# A300_Backplane.net
KiCad netlist of a schematic drawn in Altium Designer
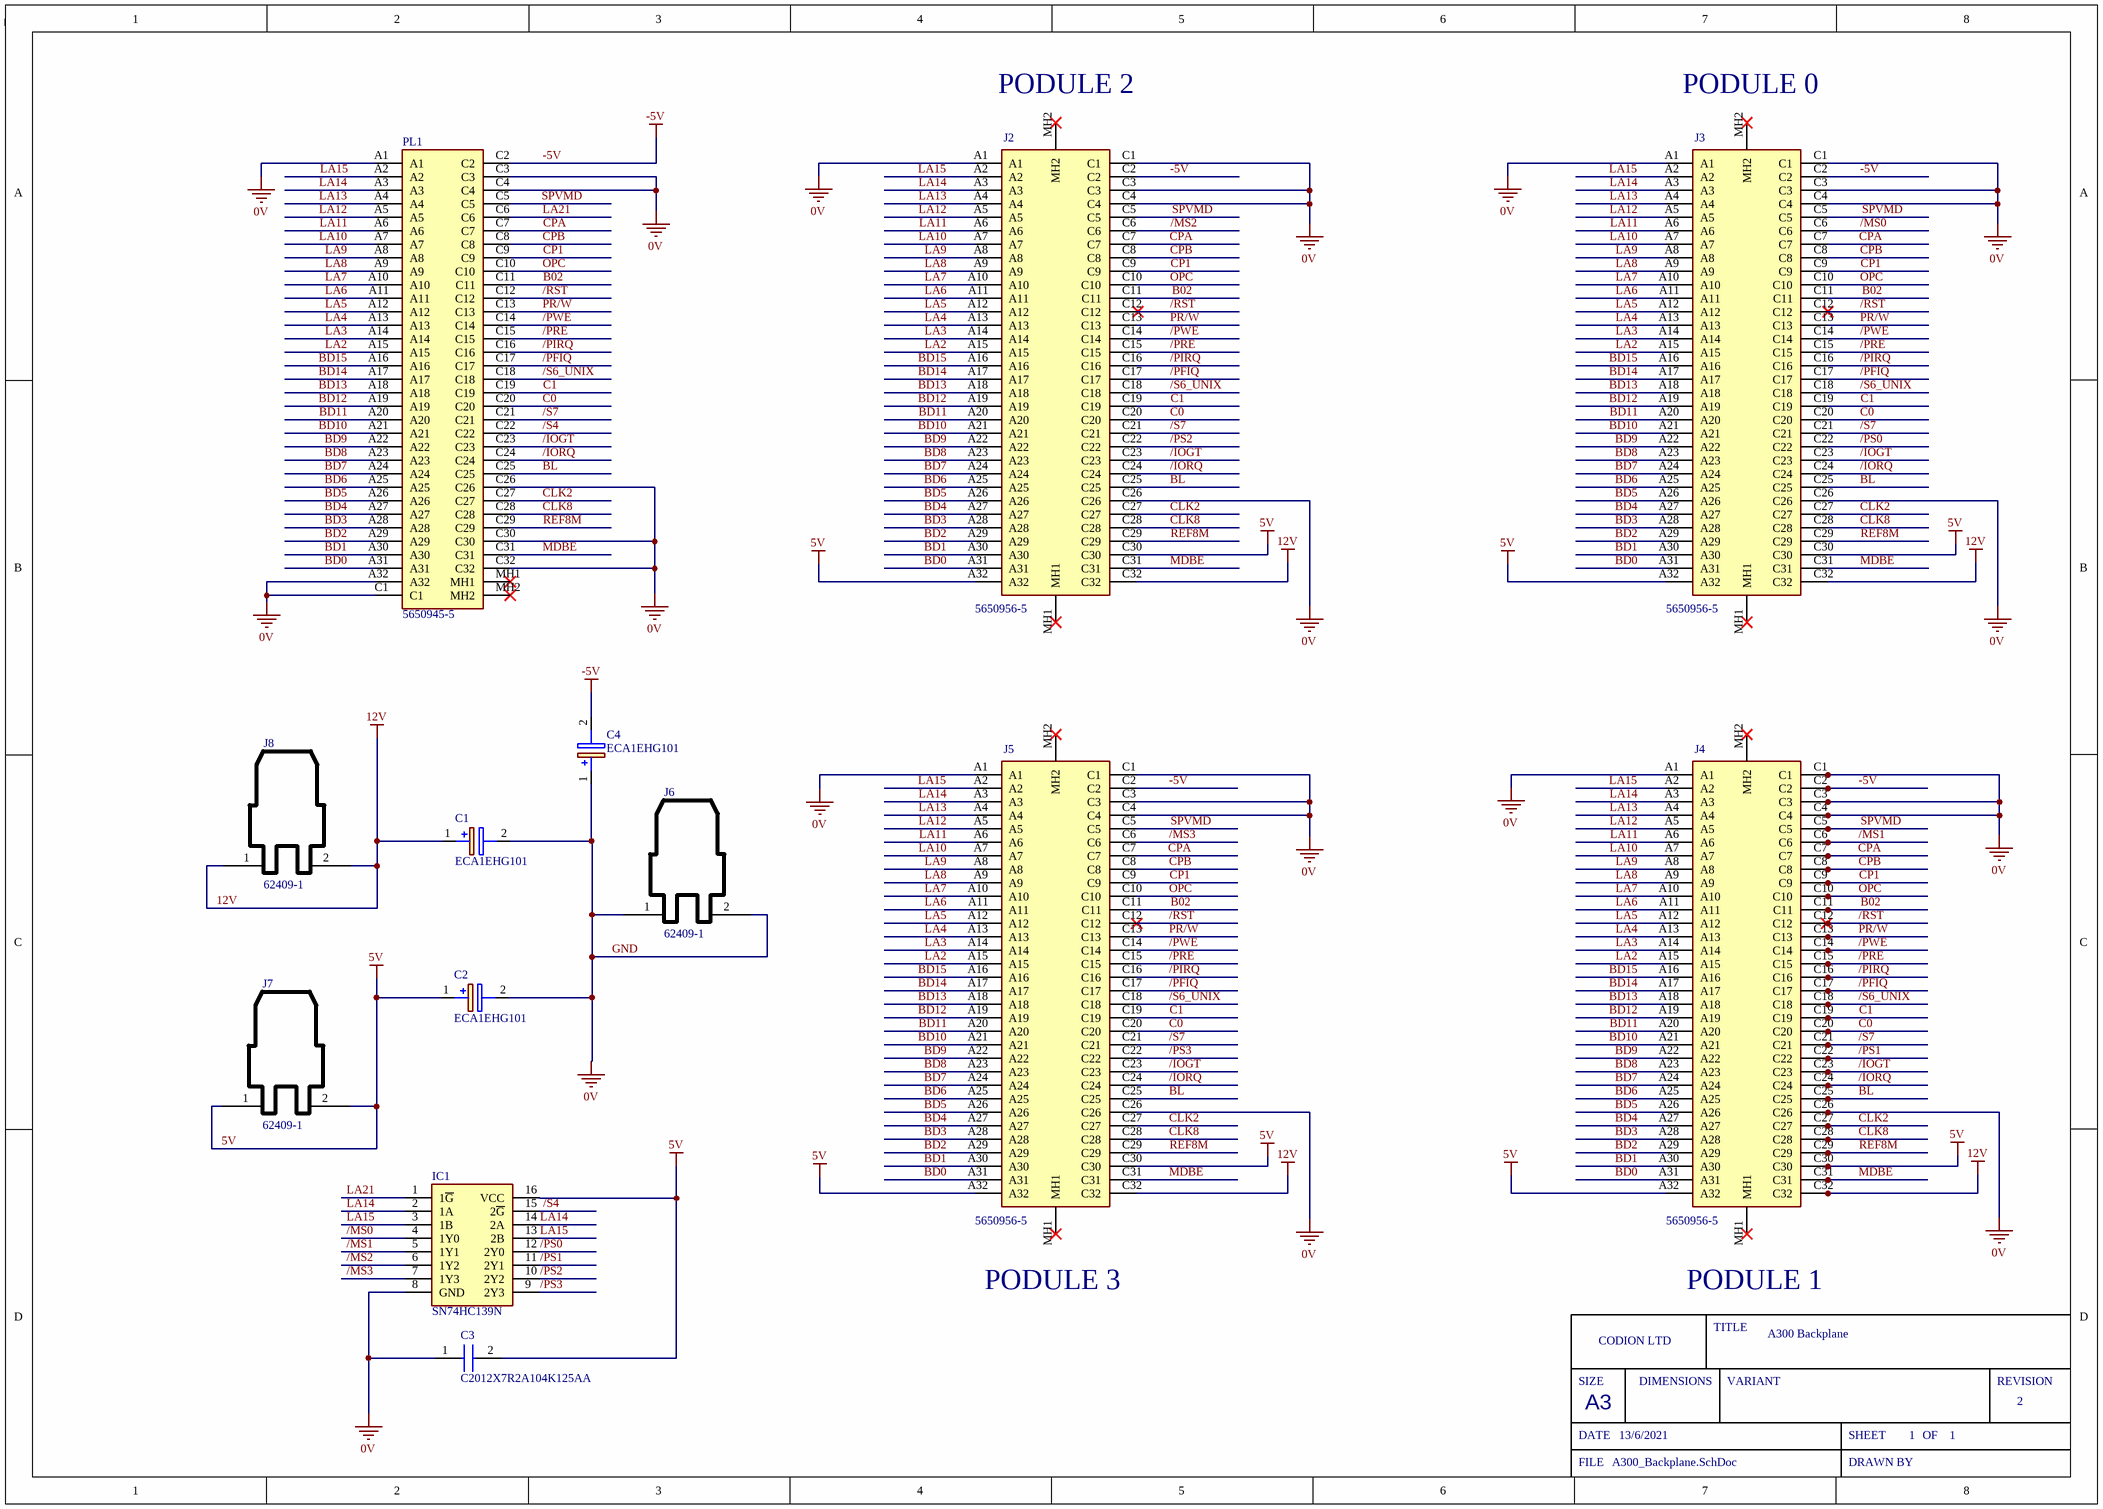
[diagram p0: A300_Backplane.SchDoc]

(export (version "E")
  (design (tool "Eeschema 10.0.6"))
  (components
    (comp (ref "C1")
      (value "ECA1EHG101")
      (footprint "SamacSys:CAPPRD250W55D630H1220")
      (description "Capacitor Polarised")
      (libsource (lib "*") (part "ECA1EHG101"))
    )
    (comp (ref "C2")
      (value "ECA1EHG101")
      (footprint "SamacSys:CAPPRD250W55D630H1220")
      (description "Capacitor Polarised")
      (libsource (lib "*") (part "ECA1EHG101"))
    )
    (comp (ref "C3")
      (value "C2012X7R2A104K125AA")
      (footprint "SamacSys:CAPC2012X145N")
      (description "Capacitor")
      (fields (field (name "MOUSER PART NUMBER") "810-C2012X7R2A104K"))
      (libsource (lib "*") (part "C2012X7R2A104K125AA"))
    )
    (comp (ref "C4")
      (value "ECA1EHG101")
      (footprint "SamacSys:CAPPRD250W55D630H1220")
      (description "Capacitor Polarised")
      (libsource (lib "") (part "ECA1EHG101_1"))
    )
    (comp (ref "IC1")
      (value "SN74HC139N")
      (footprint "SamacSys:DIP794W53P254L1930H508Q16N")
      (description "Integrated Circuit")
      (fields (field (name "MOUSER PART NUMBER") "595-SN74HC139N"))
      (libsource (lib "*") (part "SN74HC139N"))
    )
    (comp (ref "J2")
      (value "5650956-5")
      (footprint "SamacSys:56509565")
      (description "Connector")
      (fields (field (name "MOUSER PART NUMBER") "571-5650956-5"))
      (libsource (lib "*") (part "5650956-5"))
    )
    (comp (ref "J3")
      (value "5650956-5")
      (footprint "SamacSys:56509565")
      (description "Connector")
      (fields (field (name "MOUSER PART NUMBER") "571-5650956-5"))
      (libsource (lib "*") (part "5650956-5"))
    )
    (comp (ref "J4")
      (value "5650956-5")
      (footprint "SamacSys:56509565")
      (description "Connector")
      (fields (field (name "MOUSER PART NUMBER") "571-5650956-5"))
      (libsource (lib "*") (part "5650956-5"))
    )
    (comp (ref "J5")
      (value "5650956-5")
      (footprint "SamacSys:56509565")
      (description "Connector")
      (fields (field (name "MOUSER PART NUMBER") "571-5650956-5"))
      (libsource (lib "*") (part "5650956-5"))
    )
    (comp (ref "J6")
      (value "62409-1")
      (footprint "62409-1")
      (description "PCB Terminal, 6.35mm x 0.81mm, 0.25\" x 0.032\", Brass, 1.4 mm, Tin")
      (fields (field (name "PART NUMBER") "982-0022") (field (name "MANUFACTURER") "TE Coonectivity"))
      (libsource (lib "Local_Altium_Lib") (part "62409-1"))
    )
    (comp (ref "J7")
      (value "62409-1")
      (footprint "62409-1")
      (description "PCB Terminal, 6.35mm x 0.81mm, 0.25\" x 0.032\", Brass, 1.4 mm, Tin")
      (fields (field (name "PART NUMBER") "982-0022") (field (name "MANUFACTURER") "TE Coonectivity"))
      (libsource (lib "Local_Altium_Lib") (part "62409-1"))
    )
    (comp (ref "J8")
      (value "62409-1")
      (footprint "62409-1")
      (description "PCB Terminal, 6.35mm x 0.81mm, 0.25\" x 0.032\", Brass, 1.4 mm, Tin")
      (fields (field (name "PART NUMBER") "982-0022") (field (name "MANUFACTURER") "TE Coonectivity"))
      (libsource (lib "Local_Altium_Lib") (part "62409-1"))
    )
    (comp (ref "PL1")
      (value "5650945-5")
      (footprint "SamacSys:56509455")
      (description "Connector")
      (fields (field (name "MOUSER PART NUMBER") "571-5650945-5"))
      (libsource (lib "*") (part "5650945-5"))
    )
  )
  (nets
    (net (code "1") (name "-5V") (class "Default")
      (node (ref "C4") (pin "2") (pinfunction "-_2") (pintype "passive"))
      (node (ref "J2") (pin "C2") (pinfunction "C2_C2") (pintype "passive"))
      (node (ref "J3") (pin "C2") (pinfunction "C2_C2") (pintype "passive"))
      (node (ref "J4") (pin "C2") (pinfunction "C2_C2") (pintype "passive"))
      (node (ref "J5") (pin "C2") (pinfunction "C2_C2") (pintype "passive"))
      (node (ref "PL1") (pin "C2") (pinfunction "C2_C2") (pintype "passive"))
    )
    (net (code "2") (name "/B02") (class "Default")
      (node (ref "J2") (pin "C11") (pinfunction "C11_C11") (pintype "passive"))
      (node (ref "J3") (pin "C11") (pinfunction "C11_C11") (pintype "passive"))
      (node (ref "J4") (pin "C11") (pinfunction "C11_C11") (pintype "passive"))
      (node (ref "J5") (pin "C11") (pinfunction "C11_C11") (pintype "passive"))
      (node (ref "PL1") (pin "C11") (pinfunction "C11_C11") (pintype "passive"))
    )
    (net (code "3") (name "/BD0") (class "Default")
      (node (ref "J2") (pin "A31") (pinfunction "A31_A31") (pintype "passive"))
      (node (ref "J3") (pin "A31") (pinfunction "A31_A31") (pintype "passive"))
      (node (ref "J4") (pin "A31") (pinfunction "A31_A31") (pintype "passive"))
      (node (ref "J5") (pin "A31") (pinfunction "A31_A31") (pintype "passive"))
      (node (ref "PL1") (pin "A31") (pinfunction "A31_A31") (pintype "passive"))
    )
    (net (code "4") (name "/BD1") (class "Default")
      (node (ref "J2") (pin "A30") (pinfunction "A30_A30") (pintype "passive"))
      (node (ref "J3") (pin "A30") (pinfunction "A30_A30") (pintype "passive"))
      (node (ref "J4") (pin "A30") (pinfunction "A30_A30") (pintype "passive"))
      (node (ref "J5") (pin "A30") (pinfunction "A30_A30") (pintype "passive"))
      (node (ref "PL1") (pin "A30") (pinfunction "A30_A30") (pintype "passive"))
    )
    (net (code "5") (name "/BD2") (class "Default")
      (node (ref "J2") (pin "A29") (pinfunction "A29_A29") (pintype "passive"))
      (node (ref "J3") (pin "A29") (pinfunction "A29_A29") (pintype "passive"))
      (node (ref "J4") (pin "A29") (pinfunction "A29_A29") (pintype "passive"))
      (node (ref "J5") (pin "A29") (pinfunction "A29_A29") (pintype "passive"))
      (node (ref "PL1") (pin "A29") (pinfunction "A29_A29") (pintype "passive"))
    )
    (net (code "6") (name "/BD3") (class "Default")
      (node (ref "J2") (pin "A28") (pinfunction "A28_A28") (pintype "passive"))
      (node (ref "J3") (pin "A28") (pinfunction "A28_A28") (pintype "passive"))
      (node (ref "J4") (pin "A28") (pinfunction "A28_A28") (pintype "passive"))
      (node (ref "J5") (pin "A28") (pinfunction "A28_A28") (pintype "passive"))
      (node (ref "PL1") (pin "A28") (pinfunction "A28_A28") (pintype "passive"))
    )
    (net (code "7") (name "/BD4") (class "Default")
      (node (ref "J2") (pin "A27") (pinfunction "A27_A27") (pintype "passive"))
      (node (ref "J3") (pin "A27") (pinfunction "A27_A27") (pintype "passive"))
      (node (ref "J4") (pin "A27") (pinfunction "A27_A27") (pintype "passive"))
      (node (ref "J5") (pin "A27") (pinfunction "A27_A27") (pintype "passive"))
      (node (ref "PL1") (pin "A27") (pinfunction "A27_A27") (pintype "passive"))
    )
    (net (code "8") (name "/BD5") (class "Default")
      (node (ref "J2") (pin "A26") (pinfunction "A26_A26") (pintype "passive"))
      (node (ref "J3") (pin "A26") (pinfunction "A26_A26") (pintype "passive"))
      (node (ref "J4") (pin "A26") (pinfunction "A26_A26") (pintype "passive"))
      (node (ref "J5") (pin "A26") (pinfunction "A26_A26") (pintype "passive"))
      (node (ref "PL1") (pin "A26") (pinfunction "A26_A26") (pintype "passive"))
    )
    (net (code "9") (name "/BD6") (class "Default")
      (node (ref "J2") (pin "A25") (pinfunction "A25_A25") (pintype "passive"))
      (node (ref "J3") (pin "A25") (pinfunction "A25_A25") (pintype "passive"))
      (node (ref "J4") (pin "A25") (pinfunction "A25_A25") (pintype "passive"))
      (node (ref "J5") (pin "A25") (pinfunction "A25_A25") (pintype "passive"))
      (node (ref "PL1") (pin "A25") (pinfunction "A25_A25") (pintype "passive"))
    )
    (net (code "10") (name "/BD7") (class "Default")
      (node (ref "J2") (pin "A24") (pinfunction "A24_A24") (pintype "passive"))
      (node (ref "J3") (pin "A24") (pinfunction "A24_A24") (pintype "passive"))
      (node (ref "J4") (pin "A24") (pinfunction "A24_A24") (pintype "passive"))
      (node (ref "J5") (pin "A24") (pinfunction "A24_A24") (pintype "passive"))
      (node (ref "PL1") (pin "A24") (pinfunction "A24_A24") (pintype "passive"))
    )
    (net (code "11") (name "/BD8") (class "Default")
      (node (ref "J2") (pin "A23") (pinfunction "A23_A23") (pintype "passive"))
      (node (ref "J3") (pin "A23") (pinfunction "A23_A23") (pintype "passive"))
      (node (ref "J4") (pin "A23") (pinfunction "A23_A23") (pintype "passive"))
      (node (ref "J5") (pin "A23") (pinfunction "A23_A23") (pintype "passive"))
      (node (ref "PL1") (pin "A23") (pinfunction "A23_A23") (pintype "passive"))
    )
    (net (code "12") (name "/BD9") (class "Default")
      (node (ref "J2") (pin "A22") (pinfunction "A22_A22") (pintype "passive"))
      (node (ref "J3") (pin "A22") (pinfunction "A22_A22") (pintype "passive"))
      (node (ref "J4") (pin "A22") (pinfunction "A22_A22") (pintype "passive"))
      (node (ref "J5") (pin "A22") (pinfunction "A22_A22") (pintype "passive"))
      (node (ref "PL1") (pin "A22") (pinfunction "A22_A22") (pintype "passive"))
    )
    (net (code "13") (name "/BD10") (class "Default")
      (node (ref "J2") (pin "A21") (pinfunction "A21_A21") (pintype "passive"))
      (node (ref "J3") (pin "A21") (pinfunction "A21_A21") (pintype "passive"))
      (node (ref "J4") (pin "A21") (pinfunction "A21_A21") (pintype "passive"))
      (node (ref "J5") (pin "A21") (pinfunction "A21_A21") (pintype "passive"))
      (node (ref "PL1") (pin "A21") (pinfunction "A21_A21") (pintype "passive"))
    )
    (net (code "14") (name "/BD11") (class "Default")
      (node (ref "J2") (pin "A20") (pinfunction "A20_A20") (pintype "passive"))
      (node (ref "J3") (pin "A20") (pinfunction "A20_A20") (pintype "passive"))
      (node (ref "J4") (pin "A20") (pinfunction "A20_A20") (pintype "passive"))
      (node (ref "J5") (pin "A20") (pinfunction "A20_A20") (pintype "passive"))
      (node (ref "PL1") (pin "A20") (pinfunction "A20_A20") (pintype "passive"))
    )
    (net (code "15") (name "/BD12") (class "Default")
      (node (ref "J2") (pin "A19") (pinfunction "A19_A19") (pintype "passive"))
      (node (ref "J3") (pin "A19") (pinfunction "A19_A19") (pintype "passive"))
      (node (ref "J4") (pin "A19") (pinfunction "A19_A19") (pintype "passive"))
      (node (ref "J5") (pin "A19") (pinfunction "A19_A19") (pintype "passive"))
      (node (ref "PL1") (pin "A19") (pinfunction "A19_A19") (pintype "passive"))
    )
    (net (code "16") (name "/BD13") (class "Default")
      (node (ref "J2") (pin "A18") (pinfunction "A18_A18") (pintype "passive"))
      (node (ref "J3") (pin "A18") (pinfunction "A18_A18") (pintype "passive"))
      (node (ref "J4") (pin "A18") (pinfunction "A18_A18") (pintype "passive"))
      (node (ref "J5") (pin "A18") (pinfunction "A18_A18") (pintype "passive"))
      (node (ref "PL1") (pin "A18") (pinfunction "A18_A18") (pintype "passive"))
    )
    (net (code "17") (name "/BD14") (class "Default")
      (node (ref "J2") (pin "A17") (pinfunction "A17_A17") (pintype "passive"))
      (node (ref "J3") (pin "A17") (pinfunction "A17_A17") (pintype "passive"))
      (node (ref "J4") (pin "A17") (pinfunction "A17_A17") (pintype "passive"))
      (node (ref "J5") (pin "A17") (pinfunction "A17_A17") (pintype "passive"))
      (node (ref "PL1") (pin "A17") (pinfunction "A17_A17") (pintype "passive"))
    )
    (net (code "18") (name "/BD15") (class "Default")
      (node (ref "J2") (pin "A16") (pinfunction "A16_A16") (pintype "passive"))
      (node (ref "J3") (pin "A16") (pinfunction "A16_A16") (pintype "passive"))
      (node (ref "J4") (pin "A16") (pinfunction "A16_A16") (pintype "passive"))
      (node (ref "J5") (pin "A16") (pinfunction "A16_A16") (pintype "passive"))
      (node (ref "PL1") (pin "A16") (pinfunction "A16_A16") (pintype "passive"))
    )
    (net (code "19") (name "/BL") (class "Default")
      (node (ref "J2") (pin "C25") (pinfunction "C25_C25") (pintype "passive"))
      (node (ref "J3") (pin "C25") (pinfunction "C25_C25") (pintype "passive"))
      (node (ref "J4") (pin "C25") (pinfunction "C25_C25") (pintype "passive"))
      (node (ref "J5") (pin "C25") (pinfunction "C25_C25") (pintype "passive"))
      (node (ref "PL1") (pin "C25") (pinfunction "C25_C25") (pintype "passive"))
    )
    (net (code "20") (name "/C0") (class "Default")
      (node (ref "J2") (pin "C20") (pinfunction "C20_C20") (pintype "passive"))
      (node (ref "J3") (pin "C20") (pinfunction "C20_C20") (pintype "passive"))
      (node (ref "J4") (pin "C20") (pinfunction "C20_C20") (pintype "passive"))
      (node (ref "J5") (pin "C20") (pinfunction "C20_C20") (pintype "passive"))
      (node (ref "PL1") (pin "C20") (pinfunction "C20_C20") (pintype "passive"))
    )
    (net (code "21") (name "/C1") (class "Default")
      (node (ref "J2") (pin "C19") (pinfunction "C19_C19") (pintype "passive"))
      (node (ref "J3") (pin "C19") (pinfunction "C19_C19") (pintype "passive"))
      (node (ref "J4") (pin "C19") (pinfunction "C19_C19") (pintype "passive"))
      (node (ref "J5") (pin "C19") (pinfunction "C19_C19") (pintype "passive"))
      (node (ref "PL1") (pin "C19") (pinfunction "C19_C19") (pintype "passive"))
    )
    (net (code "22") (name "/CLK2") (class "Default")
      (node (ref "J2") (pin "C27") (pinfunction "C27_C27") (pintype "passive"))
      (node (ref "J3") (pin "C27") (pinfunction "C27_C27") (pintype "passive"))
      (node (ref "J4") (pin "C27") (pinfunction "C27_C27") (pintype "passive"))
      (node (ref "J5") (pin "C27") (pinfunction "C27_C27") (pintype "passive"))
      (node (ref "PL1") (pin "C27") (pinfunction "C27_C27") (pintype "passive"))
    )
    (net (code "23") (name "/CLK8") (class "Default")
      (node (ref "J2") (pin "C28") (pinfunction "C28_C28") (pintype "passive"))
      (node (ref "J3") (pin "C28") (pinfunction "C28_C28") (pintype "passive"))
      (node (ref "J4") (pin "C28") (pinfunction "C28_C28") (pintype "passive"))
      (node (ref "J5") (pin "C28") (pinfunction "C28_C28") (pintype "passive"))
      (node (ref "PL1") (pin "C28") (pinfunction "C28_C28") (pintype "passive"))
    )
    (net (code "24") (name "/CP1") (class "Default")
      (node (ref "J2") (pin "C9") (pinfunction "C9_C9") (pintype "passive"))
      (node (ref "J3") (pin "C9") (pinfunction "C9_C9") (pintype "passive"))
      (node (ref "J4") (pin "C9") (pinfunction "C9_C9") (pintype "passive"))
      (node (ref "J5") (pin "C9") (pinfunction "C9_C9") (pintype "passive"))
      (node (ref "PL1") (pin "C9") (pinfunction "C9_C9") (pintype "passive"))
    )
    (net (code "25") (name "/CPA") (class "Default")
      (node (ref "J2") (pin "C7") (pinfunction "C7_C7") (pintype "passive"))
      (node (ref "J3") (pin "C7") (pinfunction "C7_C7") (pintype "passive"))
      (node (ref "J4") (pin "C7") (pinfunction "C7_C7") (pintype "passive"))
      (node (ref "J5") (pin "C7") (pinfunction "C7_C7") (pintype "passive"))
      (node (ref "PL1") (pin "C7") (pinfunction "C7_C7") (pintype "passive"))
    )
    (net (code "26") (name "/CPB") (class "Default")
      (node (ref "J2") (pin "C8") (pinfunction "C8_C8") (pintype "passive"))
      (node (ref "J3") (pin "C8") (pinfunction "C8_C8") (pintype "passive"))
      (node (ref "J4") (pin "C8") (pinfunction "C8_C8") (pintype "passive"))
      (node (ref "J5") (pin "C8") (pinfunction "C8_C8") (pintype "passive"))
      (node (ref "PL1") (pin "C8") (pinfunction "C8_C8") (pintype "passive"))
    )
    (net (code "27") (name "/LA2") (class "Default")
      (node (ref "J2") (pin "A15") (pinfunction "A15_A15") (pintype "passive"))
      (node (ref "J3") (pin "A15") (pinfunction "A15_A15") (pintype "passive"))
      (node (ref "J4") (pin "A15") (pinfunction "A15_A15") (pintype "passive"))
      (node (ref "J5") (pin "A15") (pinfunction "A15_A15") (pintype "passive"))
      (node (ref "PL1") (pin "A15") (pinfunction "A15_A15") (pintype "passive"))
    )
    (net (code "28") (name "/LA3") (class "Default")
      (node (ref "J2") (pin "A14") (pinfunction "A14_A14") (pintype "passive"))
      (node (ref "J3") (pin "A14") (pinfunction "A14_A14") (pintype "passive"))
      (node (ref "J4") (pin "A14") (pinfunction "A14_A14") (pintype "passive"))
      (node (ref "J5") (pin "A14") (pinfunction "A14_A14") (pintype "passive"))
      (node (ref "PL1") (pin "A14") (pinfunction "A14_A14") (pintype "passive"))
    )
    (net (code "29") (name "/LA4") (class "Default")
      (node (ref "J2") (pin "A13") (pinfunction "A13_A13") (pintype "passive"))
      (node (ref "J3") (pin "A13") (pinfunction "A13_A13") (pintype "passive"))
      (node (ref "J4") (pin "A13") (pinfunction "A13_A13") (pintype "passive"))
      (node (ref "J5") (pin "A13") (pinfunction "A13_A13") (pintype "passive"))
      (node (ref "PL1") (pin "A13") (pinfunction "A13_A13") (pintype "passive"))
    )
    (net (code "30") (name "/LA5") (class "Default")
      (node (ref "J2") (pin "A12") (pinfunction "A12_A12") (pintype "passive"))
      (node (ref "J3") (pin "A12") (pinfunction "A12_A12") (pintype "passive"))
      (node (ref "J4") (pin "A12") (pinfunction "A12_A12") (pintype "passive"))
      (node (ref "J5") (pin "A12") (pinfunction "A12_A12") (pintype "passive"))
      (node (ref "PL1") (pin "A12") (pinfunction "A12_A12") (pintype "passive"))
    )
    (net (code "31") (name "/LA6") (class "Default")
      (node (ref "J2") (pin "A11") (pinfunction "A11_A11") (pintype "passive"))
      (node (ref "J3") (pin "A11") (pinfunction "A11_A11") (pintype "passive"))
      (node (ref "J4") (pin "A11") (pinfunction "A11_A11") (pintype "passive"))
      (node (ref "J5") (pin "A11") (pinfunction "A11_A11") (pintype "passive"))
      (node (ref "PL1") (pin "A11") (pinfunction "A11_A11") (pintype "passive"))
    )
    (net (code "32") (name "/LA7") (class "Default")
      (node (ref "J2") (pin "A10") (pinfunction "A10_A10") (pintype "passive"))
      (node (ref "J3") (pin "A10") (pinfunction "A10_A10") (pintype "passive"))
      (node (ref "J4") (pin "A10") (pinfunction "A10_A10") (pintype "passive"))
      (node (ref "J5") (pin "A10") (pinfunction "A10_A10") (pintype "passive"))
      (node (ref "PL1") (pin "A10") (pinfunction "A10_A10") (pintype "passive"))
    )
    (net (code "33") (name "/LA8") (class "Default")
      (node (ref "J2") (pin "A9") (pinfunction "A9_A9") (pintype "passive"))
      (node (ref "J3") (pin "A9") (pinfunction "A9_A9") (pintype "passive"))
      (node (ref "J4") (pin "A9") (pinfunction "A9_A9") (pintype "passive"))
      (node (ref "J5") (pin "A9") (pinfunction "A9_A9") (pintype "passive"))
      (node (ref "PL1") (pin "A9") (pinfunction "A9_A9") (pintype "passive"))
    )
    (net (code "34") (name "/LA9") (class "Default")
      (node (ref "J2") (pin "A8") (pinfunction "A8_A8") (pintype "passive"))
      (node (ref "J3") (pin "A8") (pinfunction "A8_A8") (pintype "passive"))
      (node (ref "J4") (pin "A8") (pinfunction "A8_A8") (pintype "passive"))
      (node (ref "J5") (pin "A8") (pinfunction "A8_A8") (pintype "passive"))
      (node (ref "PL1") (pin "A8") (pinfunction "A8_A8") (pintype "passive"))
    )
    (net (code "35") (name "/LA10") (class "Default")
      (node (ref "J2") (pin "A7") (pinfunction "A7_A7") (pintype "passive"))
      (node (ref "J3") (pin "A7") (pinfunction "A7_A7") (pintype "passive"))
      (node (ref "J4") (pin "A7") (pinfunction "A7_A7") (pintype "passive"))
      (node (ref "J5") (pin "A7") (pinfunction "A7_A7") (pintype "passive"))
      (node (ref "PL1") (pin "A7") (pinfunction "A7_A7") (pintype "passive"))
    )
    (net (code "36") (name "/LA11") (class "Default")
      (node (ref "J2") (pin "A6") (pinfunction "A6_A6") (pintype "passive"))
      (node (ref "J3") (pin "A6") (pinfunction "A6_A6") (pintype "passive"))
      (node (ref "J4") (pin "A6") (pinfunction "A6_A6") (pintype "passive"))
      (node (ref "J5") (pin "A6") (pinfunction "A6_A6") (pintype "passive"))
      (node (ref "PL1") (pin "A6") (pinfunction "A6_A6") (pintype "passive"))
    )
    (net (code "37") (name "/LA12") (class "Default")
      (node (ref "J2") (pin "A5") (pinfunction "A5_A5") (pintype "passive"))
      (node (ref "J3") (pin "A5") (pinfunction "A5_A5") (pintype "passive"))
      (node (ref "J4") (pin "A5") (pinfunction "A5_A5") (pintype "passive"))
      (node (ref "J5") (pin "A5") (pinfunction "A5_A5") (pintype "passive"))
      (node (ref "PL1") (pin "A5") (pinfunction "A5_A5") (pintype "passive"))
    )
    (net (code "38") (name "/LA13") (class "Default")
      (node (ref "J2") (pin "A4") (pinfunction "A4_A4") (pintype "passive"))
      (node (ref "J3") (pin "A4") (pinfunction "A4_A4") (pintype "passive"))
      (node (ref "J4") (pin "A4") (pinfunction "A4_A4") (pintype "passive"))
      (node (ref "J5") (pin "A4") (pinfunction "A4_A4") (pintype "passive"))
      (node (ref "PL1") (pin "A4") (pinfunction "A4_A4") (pintype "passive"))
    )
    (net (code "39") (name "/LA14") (class "Default")
      (node (ref "IC1") (pin "14") (pinfunction "2A_14") (pintype "passive"))
      (node (ref "IC1") (pin "2") (pinfunction "1A_2") (pintype "passive"))
      (node (ref "J2") (pin "A3") (pinfunction "A3_A3") (pintype "passive"))
      (node (ref "J3") (pin "A3") (pinfunction "A3_A3") (pintype "passive"))
      (node (ref "J4") (pin "A3") (pinfunction "A3_A3") (pintype "passive"))
      (node (ref "J5") (pin "A3") (pinfunction "A3_A3") (pintype "passive"))
      (node (ref "PL1") (pin "A3") (pinfunction "A3_A3") (pintype "passive"))
    )
    (net (code "40") (name "/LA15") (class "Default")
      (node (ref "IC1") (pin "13") (pinfunction "2B_13") (pintype "passive"))
      (node (ref "IC1") (pin "3") (pinfunction "1B_3") (pintype "passive"))
      (node (ref "J2") (pin "A2") (pinfunction "A2_A2") (pintype "passive"))
      (node (ref "J3") (pin "A2") (pinfunction "A2_A2") (pintype "passive"))
      (node (ref "J4") (pin "A2") (pinfunction "A2_A2") (pintype "passive"))
      (node (ref "J5") (pin "A2") (pinfunction "A2_A2") (pintype "passive"))
      (node (ref "PL1") (pin "A2") (pinfunction "A2_A2") (pintype "passive"))
    )
    (net (code "41") (name "/LA21") (class "Default")
      (node (ref "IC1") (pin "1") (pinfunction "1~{G}_1") (pintype "passive"))
      (node (ref "PL1") (pin "C6") (pinfunction "C6_C6") (pintype "passive"))
    )
    (net (code "42") (name "/MDBE") (class "Default")
      (node (ref "J2") (pin "C31") (pinfunction "C31_C31") (pintype "passive"))
      (node (ref "J3") (pin "C31") (pinfunction "C31_C31") (pintype "passive"))
      (node (ref "J4") (pin "C31") (pinfunction "C31_C31") (pintype "passive"))
      (node (ref "J5") (pin "C31") (pinfunction "C31_C31") (pintype "passive"))
      (node (ref "PL1") (pin "C31") (pinfunction "C31_C31") (pintype "passive"))
    )
    (net (code "43") (name "/OPC") (class "Default")
      (node (ref "J2") (pin "C10") (pinfunction "C10_C10") (pintype "passive"))
      (node (ref "J3") (pin "C10") (pinfunction "C10_C10") (pintype "passive"))
      (node (ref "J4") (pin "C10") (pinfunction "C10_C10") (pintype "passive"))
      (node (ref "J5") (pin "C10") (pinfunction "C10_C10") (pintype "passive"))
      (node (ref "PL1") (pin "C10") (pinfunction "C10_C10") (pintype "passive"))
    )
    (net (code "44") (name "/PR{slash}W") (class "Default")
      (node (ref "J2") (pin "C13") (pinfunction "C13_C13") (pintype "passive"))
      (node (ref "J3") (pin "C13") (pinfunction "C13_C13") (pintype "passive"))
      (node (ref "J4") (pin "C13") (pinfunction "C13_C13") (pintype "passive"))
      (node (ref "J5") (pin "C13") (pinfunction "C13_C13") (pintype "passive"))
      (node (ref "PL1") (pin "C13") (pinfunction "C13_C13") (pintype "passive"))
    )
    (net (code "45") (name "/REF8M") (class "Default")
      (node (ref "J2") (pin "C29") (pinfunction "C29_C29") (pintype "passive"))
      (node (ref "J3") (pin "C29") (pinfunction "C29_C29") (pintype "passive"))
      (node (ref "J4") (pin "C29") (pinfunction "C29_C29") (pintype "passive"))
      (node (ref "J5") (pin "C29") (pinfunction "C29_C29") (pintype "passive"))
      (node (ref "PL1") (pin "C29") (pinfunction "C29_C29") (pintype "passive"))
    )
    (net (code "46") (name "/SPVMD") (class "Default")
      (node (ref "J2") (pin "C5") (pinfunction "C5_C5") (pintype "passive"))
      (node (ref "J3") (pin "C5") (pinfunction "C5_C5") (pintype "passive"))
      (node (ref "J4") (pin "C5") (pinfunction "C5_C5") (pintype "passive"))
      (node (ref "J5") (pin "C5") (pinfunction "C5_C5") (pintype "passive"))
      (node (ref "PL1") (pin "C5") (pinfunction "C5_C5") (pintype "passive"))
    )
    (net (code "47") (name "/{slash}IOGT") (class "Default")
      (node (ref "J2") (pin "C23") (pinfunction "C23_C23") (pintype "passive"))
      (node (ref "J3") (pin "C23") (pinfunction "C23_C23") (pintype "passive"))
      (node (ref "J4") (pin "C23") (pinfunction "C23_C23") (pintype "passive"))
      (node (ref "J5") (pin "C23") (pinfunction "C23_C23") (pintype "passive"))
      (node (ref "PL1") (pin "C23") (pinfunction "C23_C23") (pintype "passive"))
    )
    (net (code "48") (name "/{slash}IORQ") (class "Default")
      (node (ref "J2") (pin "C24") (pinfunction "C24_C24") (pintype "passive"))
      (node (ref "J3") (pin "C24") (pinfunction "C24_C24") (pintype "passive"))
      (node (ref "J4") (pin "C24") (pinfunction "C24_C24") (pintype "passive"))
      (node (ref "J5") (pin "C24") (pinfunction "C24_C24") (pintype "passive"))
      (node (ref "PL1") (pin "C24") (pinfunction "C24_C24") (pintype "passive"))
    )
    (net (code "49") (name "/{slash}MS0") (class "Default")
      (node (ref "IC1") (pin "4") (pinfunction "1Y0_4") (pintype "passive"))
      (node (ref "J3") (pin "C6") (pinfunction "C6_C6") (pintype "passive"))
    )
    (net (code "50") (name "/{slash}MS1") (class "Default")
      (node (ref "IC1") (pin "5") (pinfunction "1Y1_5") (pintype "passive"))
      (node (ref "J4") (pin "C6") (pinfunction "C6_C6") (pintype "passive"))
    )
    (net (code "51") (name "/{slash}MS2") (class "Default")
      (node (ref "IC1") (pin "6") (pinfunction "1Y2_6") (pintype "passive"))
      (node (ref "J2") (pin "C6") (pinfunction "C6_C6") (pintype "passive"))
    )
    (net (code "52") (name "/{slash}MS3") (class "Default")
      (node (ref "IC1") (pin "7") (pinfunction "1Y3_7") (pintype "passive"))
      (node (ref "J5") (pin "C6") (pinfunction "C6_C6") (pintype "passive"))
    )
    (net (code "53") (name "/{slash}PFIQ") (class "Default")
      (node (ref "J2") (pin "C17") (pinfunction "C17_C17") (pintype "passive"))
      (node (ref "J3") (pin "C17") (pinfunction "C17_C17") (pintype "passive"))
      (node (ref "J4") (pin "C17") (pinfunction "C17_C17") (pintype "passive"))
      (node (ref "J5") (pin "C17") (pinfunction "C17_C17") (pintype "passive"))
      (node (ref "PL1") (pin "C17") (pinfunction "C17_C17") (pintype "passive"))
    )
    (net (code "54") (name "/{slash}PIRQ") (class "Default")
      (node (ref "J2") (pin "C16") (pinfunction "C16_C16") (pintype "passive"))
      (node (ref "J3") (pin "C16") (pinfunction "C16_C16") (pintype "passive"))
      (node (ref "J4") (pin "C16") (pinfunction "C16_C16") (pintype "passive"))
      (node (ref "J5") (pin "C16") (pinfunction "C16_C16") (pintype "passive"))
      (node (ref "PL1") (pin "C16") (pinfunction "C16_C16") (pintype "passive"))
    )
    (net (code "55") (name "/{slash}PRE") (class "Default")
      (node (ref "J2") (pin "C15") (pinfunction "C15_C15") (pintype "passive"))
      (node (ref "J3") (pin "C15") (pinfunction "C15_C15") (pintype "passive"))
      (node (ref "J4") (pin "C15") (pinfunction "C15_C15") (pintype "passive"))
      (node (ref "J5") (pin "C15") (pinfunction "C15_C15") (pintype "passive"))
      (node (ref "PL1") (pin "C15") (pinfunction "C15_C15") (pintype "passive"))
    )
    (net (code "56") (name "/{slash}PS0") (class "Default")
      (node (ref "IC1") (pin "12") (pinfunction "2Y0_12") (pintype "passive"))
      (node (ref "J3") (pin "C22") (pinfunction "C22_C22") (pintype "passive"))
    )
    (net (code "57") (name "/{slash}PS1") (class "Default")
      (node (ref "IC1") (pin "11") (pinfunction "2Y1_11") (pintype "passive"))
      (node (ref "J4") (pin "C22") (pinfunction "C22_C22") (pintype "passive"))
    )
    (net (code "58") (name "/{slash}PS2") (class "Default")
      (node (ref "IC1") (pin "10") (pinfunction "2Y2_10") (pintype "passive"))
      (node (ref "J2") (pin "C22") (pinfunction "C22_C22") (pintype "passive"))
    )
    (net (code "59") (name "/{slash}PS3") (class "Default")
      (node (ref "IC1") (pin "9") (pinfunction "2Y3_9") (pintype "passive"))
      (node (ref "J5") (pin "C22") (pinfunction "C22_C22") (pintype "passive"))
    )
    (net (code "60") (name "/{slash}PWE") (class "Default")
      (node (ref "J2") (pin "C14") (pinfunction "C14_C14") (pintype "passive"))
      (node (ref "J3") (pin "C14") (pinfunction "C14_C14") (pintype "passive"))
      (node (ref "J4") (pin "C14") (pinfunction "C14_C14") (pintype "passive"))
      (node (ref "J5") (pin "C14") (pinfunction "C14_C14") (pintype "passive"))
      (node (ref "PL1") (pin "C14") (pinfunction "C14_C14") (pintype "passive"))
    )
    (net (code "61") (name "/{slash}RST") (class "Default")
      (node (ref "J2") (pin "C12") (pinfunction "C12_C12") (pintype "passive"))
      (node (ref "J3") (pin "C12") (pinfunction "C12_C12") (pintype "passive"))
      (node (ref "J4") (pin "C12") (pinfunction "C12_C12") (pintype "passive"))
      (node (ref "J5") (pin "C12") (pinfunction "C12_C12") (pintype "passive"))
      (node (ref "PL1") (pin "C12") (pinfunction "C12_C12") (pintype "passive"))
    )
    (net (code "62") (name "/{slash}S4") (class "Default")
      (node (ref "IC1") (pin "15") (pinfunction "2~{G}_15") (pintype "passive"))
      (node (ref "PL1") (pin "C22") (pinfunction "C22_C22") (pintype "passive"))
    )
    (net (code "63") (name "/{slash}S6_UNIX") (class "Default")
      (node (ref "J2") (pin "C18") (pinfunction "C18_C18") (pintype "passive"))
      (node (ref "J3") (pin "C18") (pinfunction "C18_C18") (pintype "passive"))
      (node (ref "J4") (pin "C18") (pinfunction "C18_C18") (pintype "passive"))
      (node (ref "J5") (pin "C18") (pinfunction "C18_C18") (pintype "passive"))
      (node (ref "PL1") (pin "C18") (pinfunction "C18_C18") (pintype "passive"))
    )
    (net (code "64") (name "/{slash}S7") (class "Default")
      (node (ref "J2") (pin "C21") (pinfunction "C21_C21") (pintype "passive"))
      (node (ref "J3") (pin "C21") (pinfunction "C21_C21") (pintype "passive"))
      (node (ref "J4") (pin "C21") (pinfunction "C21_C21") (pintype "passive"))
      (node (ref "J5") (pin "C21") (pinfunction "C21_C21") (pintype "passive"))
      (node (ref "PL1") (pin "C21") (pinfunction "C21_C21") (pintype "passive"))
    )
    (net (code "65") (name "0V") (class "Default")
      (node (ref "C1") (pin "2") (pinfunction "-_2") (pintype "passive"))
      (node (ref "C2") (pin "2") (pinfunction "-_2") (pintype "passive"))
      (node (ref "C3") (pin "1") (pinfunction "1_1") (pintype "passive"))
      (node (ref "C4") (pin "1") (pinfunction "+_1") (pintype "passive"))
      (node (ref "IC1") (pin "8") (pinfunction "GND_8") (pintype "passive"))
      (node (ref "J2") (pin "A1") (pinfunction "A1_A1") (pintype "passive"))
      (node (ref "J2") (pin "C1") (pinfunction "C1_C1") (pintype "passive"))
      (node (ref "J2") (pin "C26") (pinfunction "C26_C26") (pintype "passive"))
      (node (ref "J2") (pin "C3") (pinfunction "C3_C3") (pintype "passive"))
      (node (ref "J2") (pin "C4") (pinfunction "C4_C4") (pintype "passive"))
      (node (ref "J3") (pin "A1") (pinfunction "A1_A1") (pintype "passive"))
      (node (ref "J3") (pin "C1") (pinfunction "C1_C1") (pintype "passive"))
      (node (ref "J3") (pin "C26") (pinfunction "C26_C26") (pintype "passive"))
      (node (ref "J3") (pin "C3") (pinfunction "C3_C3") (pintype "passive"))
      (node (ref "J3") (pin "C4") (pinfunction "C4_C4") (pintype "passive"))
      (node (ref "J4") (pin "A1") (pinfunction "A1_A1") (pintype "passive"))
      (node (ref "J4") (pin "C1") (pinfunction "C1_C1") (pintype "passive"))
      (node (ref "J4") (pin "C26") (pinfunction "C26_C26") (pintype "passive"))
      (node (ref "J4") (pin "C3") (pinfunction "C3_C3") (pintype "passive"))
      (node (ref "J4") (pin "C4") (pinfunction "C4_C4") (pintype "passive"))
      (node (ref "J5") (pin "A1") (pinfunction "A1_A1") (pintype "passive"))
      (node (ref "J5") (pin "C1") (pinfunction "C1_C1") (pintype "passive"))
      (node (ref "J5") (pin "C26") (pinfunction "C26_C26") (pintype "passive"))
      (node (ref "J5") (pin "C3") (pinfunction "C3_C3") (pintype "passive"))
      (node (ref "J5") (pin "C4") (pinfunction "C4_C4") (pintype "passive"))
      (node (ref "J6") (pin "1") (pintype "power_in"))
      (node (ref "J6") (pin "2") (pintype "power_in"))
      (node (ref "PL1") (pin "A1") (pinfunction "A1_A1") (pintype "passive"))
      (node (ref "PL1") (pin "A32") (pinfunction "A32_A32") (pintype "passive"))
      (node (ref "PL1") (pin "C1") (pinfunction "C1_C1") (pintype "passive"))
      (node (ref "PL1") (pin "C26") (pinfunction "C26_C26") (pintype "passive"))
      (node (ref "PL1") (pin "C3") (pinfunction "C3_C3") (pintype "passive"))
      (node (ref "PL1") (pin "C30") (pinfunction "C30_C30") (pintype "passive"))
      (node (ref "PL1") (pin "C32") (pinfunction "C32_C32") (pintype "passive"))
      (node (ref "PL1") (pin "C4") (pinfunction "C4_C4") (pintype "passive"))
    )
    (net (code "66") (name "5V") (class "Default")
      (node (ref "C2") (pin "1") (pinfunction "+_1") (pintype "passive"))
      (node (ref "C3") (pin "2") (pinfunction "2_2") (pintype "passive"))
      (node (ref "IC1") (pin "16") (pinfunction "VCC_16") (pintype "passive"))
      (node (ref "J2") (pin "A32") (pinfunction "A32_A32") (pintype "passive"))
      (node (ref "J2") (pin "C30") (pinfunction "C30_C30") (pintype "passive"))
      (node (ref "J3") (pin "A32") (pinfunction "A32_A32") (pintype "passive"))
      (node (ref "J3") (pin "C30") (pinfunction "C30_C30") (pintype "passive"))
      (node (ref "J4") (pin "A32") (pinfunction "A32_A32") (pintype "passive"))
      (node (ref "J4") (pin "C30") (pinfunction "C30_C30") (pintype "passive"))
      (node (ref "J5") (pin "A32") (pinfunction "A32_A32") (pintype "passive"))
      (node (ref "J5") (pin "C30") (pinfunction "C30_C30") (pintype "passive"))
      (node (ref "J7") (pin "1") (pintype "power_in"))
      (node (ref "J7") (pin "2") (pintype "power_in"))
    )
    (net (code "67") (name "12V") (class "Default")
      (node (ref "C1") (pin "1") (pinfunction "+_1") (pintype "passive"))
      (node (ref "J2") (pin "C32") (pinfunction "C32_C32") (pintype "passive"))
      (node (ref "J3") (pin "C32") (pinfunction "C32_C32") (pintype "passive"))
      (node (ref "J4") (pin "C32") (pinfunction "C32_C32") (pintype "passive"))
      (node (ref "J5") (pin "C32") (pinfunction "C32_C32") (pintype "passive"))
      (node (ref "J8") (pin "1") (pintype "power_in"))
      (node (ref "J8") (pin "2") (pintype "power_in"))
    )
    (net (code "68") (name "unconnected-(J2-PadMH1)") (class "Default")
      (node (ref "J2") (pin "MH1") (pinfunction "MH1_MH1") (pintype "passive+no_connect"))
    )
    (net (code "69") (name "unconnected-(J2-PadMH2)") (class "Default")
      (node (ref "J2") (pin "MH2") (pinfunction "MH2_MH2") (pintype "passive+no_connect"))
    )
    (net (code "70") (name "unconnected-(J3-PadMH1)") (class "Default")
      (node (ref "J3") (pin "MH1") (pinfunction "MH1_MH1") (pintype "passive+no_connect"))
    )
    (net (code "71") (name "unconnected-(J3-PadMH2)") (class "Default")
      (node (ref "J3") (pin "MH2") (pinfunction "MH2_MH2") (pintype "passive+no_connect"))
    )
    (net (code "72") (name "unconnected-(J4-PadMH1)") (class "Default")
      (node (ref "J4") (pin "MH1") (pinfunction "MH1_MH1") (pintype "passive+no_connect"))
    )
    (net (code "73") (name "unconnected-(J4-PadMH2)") (class "Default")
      (node (ref "J4") (pin "MH2") (pinfunction "MH2_MH2") (pintype "passive+no_connect"))
    )
    (net (code "74") (name "unconnected-(J5-PadMH1)") (class "Default")
      (node (ref "J5") (pin "MH1") (pinfunction "MH1_MH1") (pintype "passive+no_connect"))
    )
    (net (code "75") (name "unconnected-(J5-PadMH2)") (class "Default")
      (node (ref "J5") (pin "MH2") (pinfunction "MH2_MH2") (pintype "passive+no_connect"))
    )
    (net (code "76") (name "unconnected-(PL1-PadMH1)") (class "Default")
      (node (ref "PL1") (pin "MH1") (pinfunction "MH1_MH1") (pintype "passive+no_connect"))
    )
    (net (code "77") (name "unconnected-(PL1-PadMH2)") (class "Default")
      (node (ref "PL1") (pin "MH2") (pinfunction "MH2_MH2") (pintype "passive+no_connect"))
    )
  )
)
